# Sheet3.net
KiCad netlist of a schematic drawn in Altium Designer
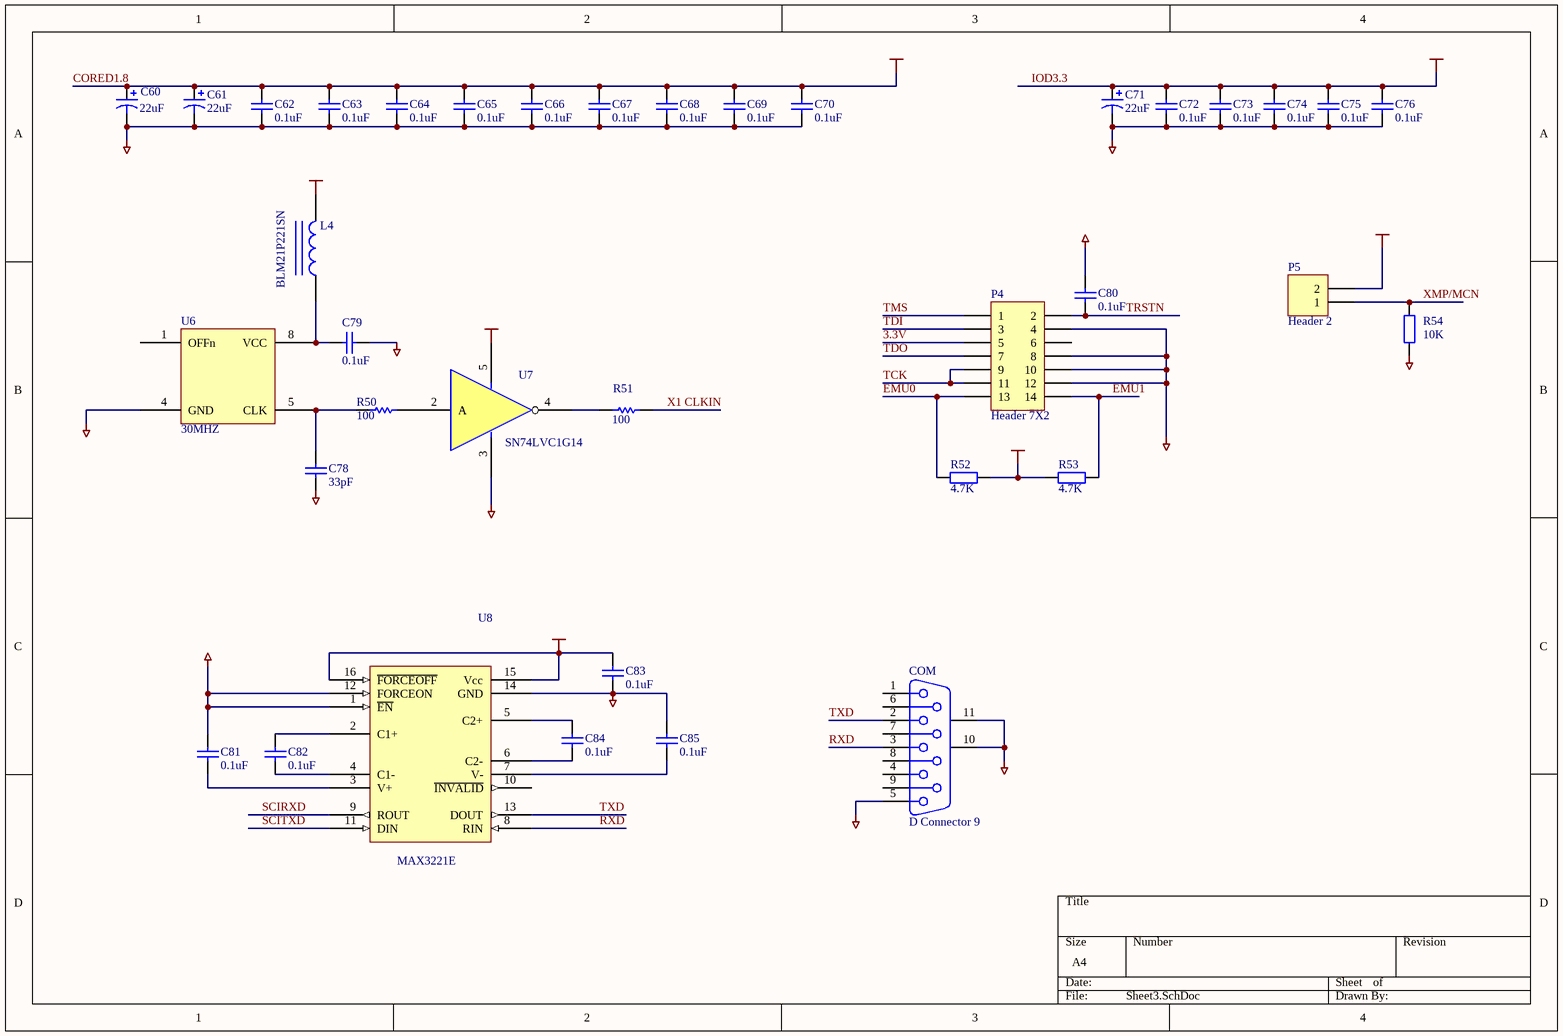
[diagram p0: Sheet3.SchDoc]

(export (version "E")
  (design (tool "Eeschema 10.0.6"))
  (components
    (comp (ref "C60")
      (value "22uF")
      (footprint "CA2222-0350")
      (description "Polarized Capacitor (Surface Mount)")
      (fields (field (name "PUBLISHER") "Altium Limited"))
      (libsource (lib "Miscellaneous Devices") (part "Cap Pol3"))
    )
    (comp (ref "C61")
      (value "22uF")
      (footprint "CA2222-0350")
      (description "Polarized Capacitor (Surface Mount)")
      (fields (field (name "PUBLISHER") "Altium Limited"))
      (libsource (lib "Miscellaneous Devices") (part "Cap Pol3"))
    )
    (comp (ref "C62")
      (value "0.1uF")
      (footprint "CC2012-0805")
      (description "Capacitor (Semiconductor SIM Model)")
      (fields (field (name "PUBLISHER") "Altium Limited"))
      (libsource (lib "Miscellaneous Devices") (part "Cap Semi"))
    )
    (comp (ref "C63")
      (value "0.1uF")
      (footprint "CC2012-0805")
      (description "Capacitor (Semiconductor SIM Model)")
      (fields (field (name "PUBLISHER") "Altium Limited"))
      (libsource (lib "Miscellaneous Devices") (part "Cap Semi"))
    )
    (comp (ref "C64")
      (value "0.1uF")
      (footprint "CC2012-0805")
      (description "Capacitor (Semiconductor SIM Model)")
      (fields (field (name "PUBLISHER") "Altium Limited"))
      (libsource (lib "Miscellaneous Devices") (part "Cap Semi"))
    )
    (comp (ref "C65")
      (value "0.1uF")
      (footprint "CC2012-0805")
      (description "Capacitor (Semiconductor SIM Model)")
      (fields (field (name "PUBLISHER") "Altium Limited"))
      (libsource (lib "Miscellaneous Devices") (part "Cap Semi"))
    )
    (comp (ref "C66")
      (value "0.1uF")
      (footprint "CC2012-0805")
      (description "Capacitor (Semiconductor SIM Model)")
      (fields (field (name "PUBLISHER") "Altium Limited"))
      (libsource (lib "Miscellaneous Devices") (part "Cap Semi"))
    )
    (comp (ref "C67")
      (value "0.1uF")
      (footprint "CC2012-0805")
      (description "Capacitor (Semiconductor SIM Model)")
      (fields (field (name "PUBLISHER") "Altium Limited"))
      (libsource (lib "Miscellaneous Devices") (part "Cap Semi"))
    )
    (comp (ref "C68")
      (value "0.1uF")
      (footprint "CC2012-0805")
      (description "Capacitor (Semiconductor SIM Model)")
      (fields (field (name "PUBLISHER") "Altium Limited"))
      (libsource (lib "Miscellaneous Devices") (part "Cap Semi"))
    )
    (comp (ref "C69")
      (value "0.1uF")
      (footprint "CC2012-0805")
      (description "Capacitor (Semiconductor SIM Model)")
      (fields (field (name "PUBLISHER") "Altium Limited"))
      (libsource (lib "Miscellaneous Devices") (part "Cap Semi"))
    )
    (comp (ref "C70")
      (value "0.1uF")
      (footprint "CC2012-0805")
      (description "Capacitor (Semiconductor SIM Model)")
      (fields (field (name "PUBLISHER") "Altium Limited"))
      (libsource (lib "Miscellaneous Devices") (part "Cap Semi"))
    )
    (comp (ref "C71")
      (value "22uF")
      (footprint "CA2222-0350")
      (description "Polarized Capacitor (Surface Mount)")
      (fields (field (name "PUBLISHER") "Altium Limited"))
      (libsource (lib "Miscellaneous Devices") (part "Cap Pol3"))
    )
    (comp (ref "C72")
      (value "0.1uF")
      (footprint "CC2012-0805")
      (description "Capacitor (Semiconductor SIM Model)")
      (fields (field (name "PUBLISHER") "Altium Limited"))
      (libsource (lib "Miscellaneous Devices") (part "Cap Semi"))
    )
    (comp (ref "C73")
      (value "0.1uF")
      (footprint "CC2012-0805")
      (description "Capacitor (Semiconductor SIM Model)")
      (fields (field (name "PUBLISHER") "Altium Limited"))
      (libsource (lib "Miscellaneous Devices") (part "Cap Semi"))
    )
    (comp (ref "C74")
      (value "0.1uF")
      (footprint "CC2012-0805")
      (description "Capacitor (Semiconductor SIM Model)")
      (fields (field (name "PUBLISHER") "Altium Limited"))
      (libsource (lib "Miscellaneous Devices") (part "Cap Semi"))
    )
    (comp (ref "C75")
      (value "0.1uF")
      (footprint "CC2012-0805")
      (description "Capacitor (Semiconductor SIM Model)")
      (fields (field (name "PUBLISHER") "Altium Limited"))
      (libsource (lib "Miscellaneous Devices") (part "Cap Semi"))
    )
    (comp (ref "C76")
      (value "0.1uF")
      (footprint "CC2012-0805")
      (description "Capacitor")
      (fields (field (name "PUBLISHER") "Altium Limited"))
      (libsource (lib "Miscellaneous Devices") (part "Cap"))
    )
    (comp (ref "C78")
      (value "33pF")
      (footprint "CC2012-0805")
      (description "Capacitor")
      (fields (field (name "PUBLISHER") "Altium Limited"))
      (libsource (lib "Miscellaneous Devices") (part "Cap"))
    )
    (comp (ref "C79")
      (value "0.1uF")
      (footprint "CC2012-0805")
      (description "Capacitor (Semiconductor SIM Model)")
      (fields (field (name "PUBLISHER") "Altium Limited"))
      (libsource (lib "Miscellaneous Devices") (part "Cap Semi"))
    )
    (comp (ref "C80")
      (value "0.1uF")
      (footprint "CC2012-0805")
      (description "Capacitor")
      (fields (field (name "PUBLISHER") "Altium Limited"))
      (libsource (lib "Miscellaneous Devices") (part "Cap"))
    )
    (comp (ref "C81")
      (value "0.1uF")
      (footprint "CC2012-0805")
      (description "Capacitor (Semiconductor SIM Model)")
      (fields (field (name "PUBLISHER") "Altium Limited"))
      (libsource (lib "Miscellaneous Devices") (part "Cap Semi"))
    )
    (comp (ref "C82")
      (value "0.1uF")
      (footprint "CC2012-0805")
      (description "Capacitor (Semiconductor SIM Model)")
      (fields (field (name "PUBLISHER") "Altium Limited"))
      (libsource (lib "Miscellaneous Devices") (part "Cap Semi"))
    )
    (comp (ref "C83")
      (value "0.1uF")
      (footprint "CC2012-0805")
      (description "Capacitor (Semiconductor SIM Model)")
      (fields (field (name "PUBLISHER") "Altium Limited"))
      (libsource (lib "Miscellaneous Devices") (part "Cap Semi"))
    )
    (comp (ref "C84")
      (value "0.1uF")
      (footprint "CC2012-0805")
      (description "Capacitor (Semiconductor SIM Model)")
      (fields (field (name "PUBLISHER") "Altium Limited"))
      (libsource (lib "Miscellaneous Devices") (part "Cap Semi"))
    )
    (comp (ref "C85")
      (value "0.1uF")
      (footprint "CC2012-0805")
      (description "Capacitor (Semiconductor SIM Model)")
      (fields (field (name "PUBLISHER") "Altium Limited"))
      (libsource (lib "Miscellaneous Devices") (part "Cap Semi"))
    )
    (comp (ref "COM")
      (value "D Connector 9")
      (footprint "DSUB1.385-2H9")
      (description "Receptacle Assembly, 9 Position, Right Angle")
      (fields (field (name "PUBLISHER") "Altium Limited"))
      (libsource (lib "Miscellaneous Connectors") (part "D Connector 9"))
    )
    (comp (ref "L4")
      (value "BLM21P221SN")
      (footprint "CR2012-0805")
      (description "Magnetic-Core Inductor")
      (fields (field (name "PUBLISHER") "Altium Limited"))
      (libsource (lib "Miscellaneous Devices") (part "Inductor Iron"))
    )
    (comp (ref "P4")
      (value "Header 7X2")
      (footprint "HDR2X7")
      (description "Header, 7-Pin, Dual row")
      (fields (field (name "PUBLISHER") "Altium Limited"))
      (libsource (lib "Miscellaneous Connectors") (part "Header 7X2"))
    )
    (comp (ref "P5")
      (value "Header 2")
      (footprint "HDR1X2")
      (description "Header, 2-Pin")
      (fields (field (name "PUBLISHER") "Altium Limited"))
      (libsource (lib "Miscellaneous Connectors") (part "Header 2"))
    )
    (comp (ref "R50")
      (value "100")
      (footprint "CR2012-0805")
      (description "Resistor")
      (fields (field (name "PUBLISHER") "Altium Limited"))
      (libsource (lib "Miscellaneous Devices") (part "Res1"))
    )
    (comp (ref "R51")
      (value "100")
      (footprint "CR2012-0805")
      (description "Resistor")
      (fields (field (name "PUBLISHER") "Altium Limited"))
      (libsource (lib "Miscellaneous Devices") (part "Res1"))
    )
    (comp (ref "R52")
      (value "4.7K")
      (footprint "CR2012-0805")
      (description "Resistor")
      (fields (field (name "PUBLISHER") "Altium Limited"))
      (libsource (lib "") (part "Res2_1"))
    )
    (comp (ref "R53")
      (value "4.7K")
      (footprint "CR2012-0805")
      (description "Resistor")
      (fields (field (name "PUBLISHER") "Altium Limited"))
      (libsource (lib "") (part "Res2_1"))
    )
    (comp (ref "R54")
      (value "10K")
      (footprint "CR2012-0805")
      (description "Resistor")
      (fields (field (name "PUBLISHER") "Altium Limited"))
      (libsource (lib "Miscellaneous Devices") (part "Res2"))
    )
    (comp (ref "U6")
      (value "30MHZ")
      (footprint "CR1525-4850")
      (description "有源晶振")
      (libsource (lib "MyIntLib") (part "Crystal"))
    )
    (comp (ref "U7")
      (value "SN74LVC1G14")
      (footprint "SC-70")
      (libsource (lib "MyIntLib") (part "SN74LVC1G14"))
    )
    (comp (ref "U8") (value "MAX3221E") (footprint "PW16") (libsource (lib "Schlib1") (part "MAX3221E")))
  )
  (nets
    (net (code "1") (name "/EMU0") (class "Default")
      (node (ref "P4") (pin "13") (pinfunction "13_13") (pintype "passive"))
      (node (ref "R52") (pin "1") (pinfunction "1_1") (pintype "passive"))
    )
    (net (code "2") (name "/EMU1") (class "Default")
      (node (ref "P4") (pin "14") (pinfunction "14_14") (pintype "passive"))
      (node (ref "R53") (pin "2") (pinfunction "2_2") (pintype "passive"))
    )
    (net (code "3") (name "/RXD") (class "Default")
      (node (ref "COM") (pin "3") (pinfunction "3_3") (pintype "passive"))
      (node (ref "U8") (pin "8") (pinfunction "RIN_8") (pintype "input"))
    )
    (net (code "4") (name "/SCIRXD") (class "Default")
      (node (ref "U8") (pin "9") (pinfunction "ROUT_9") (pintype "output"))
    )
    (net (code "5") (name "/SCITXD") (class "Default")
      (node (ref "U8") (pin "11") (pinfunction "DIN_11") (pintype "input"))
    )
    (net (code "6") (name "/TCK") (class "Default")
      (node (ref "P4") (pin "11") (pinfunction "11_11") (pintype "passive"))
      (node (ref "P4") (pin "9") (pinfunction "9_9") (pintype "passive"))
    )
    (net (code "7") (name "/TDI") (class "Default")
      (node (ref "P4") (pin "3") (pinfunction "3_3") (pintype "passive"))
    )
    (net (code "8") (name "/TDO") (class "Default")
      (node (ref "P4") (pin "7") (pinfunction "7_7") (pintype "passive"))
    )
    (net (code "9") (name "/TMS") (class "Default")
      (node (ref "P4") (pin "1") (pinfunction "1_1") (pintype "passive"))
    )
    (net (code "10") (name "/TRSTN") (class "Default")
      (node (ref "C80") (pin "1") (pinfunction "1_1") (pintype "passive"))
      (node (ref "P4") (pin "2") (pinfunction "2_2") (pintype "passive"))
    )
    (net (code "11") (name "/TXD") (class "Default")
      (node (ref "COM") (pin "2") (pinfunction "2_2") (pintype "passive"))
      (node (ref "U8") (pin "13") (pinfunction "DOUT_13") (pintype "output"))
    )
    (net (code "12") (name "/X1 CLKIN") (class "Default")
      (node (ref "R51") (pin "2") (pinfunction "2_2") (pintype "passive"))
    )
    (net (code "13") (name "/XMP{slash}MCN") (class "Default")
      (node (ref "P5") (pin "1") (pinfunction "1_1") (pintype "passive"))
      (node (ref "R54") (pin "2") (pinfunction "2_2") (pintype "passive"))
    )
    (net (code "14") (name "1.8V") (class "Default")
      (node (ref "C60") (pin "1") (pinfunction "1_1") (pintype "passive"))
      (node (ref "C61") (pin "1") (pinfunction "1_1") (pintype "passive"))
      (node (ref "C62") (pin "2") (pinfunction "2_2") (pintype "passive"))
      (node (ref "C63") (pin "2") (pinfunction "2_2") (pintype "passive"))
      (node (ref "C64") (pin "2") (pinfunction "2_2") (pintype "passive"))
      (node (ref "C65") (pin "2") (pinfunction "2_2") (pintype "passive"))
      (node (ref "C66") (pin "2") (pinfunction "2_2") (pintype "passive"))
      (node (ref "C67") (pin "2") (pinfunction "2_2") (pintype "passive"))
      (node (ref "C68") (pin "2") (pinfunction "2_2") (pintype "passive"))
      (node (ref "C69") (pin "2") (pinfunction "2_2") (pintype "passive"))
      (node (ref "C70") (pin "2") (pinfunction "2_2") (pintype "passive"))
      (node (ref "U7") (pin "5") (pinfunction "VCC_5") (pintype "power_in"))
    )
    (net (code "15") (name "3.3V") (class "Default")
      (node (ref "C71") (pin "1") (pinfunction "1_1") (pintype "passive"))
      (node (ref "C72") (pin "2") (pinfunction "2_2") (pintype "passive"))
      (node (ref "C73") (pin "2") (pinfunction "2_2") (pintype "passive"))
      (node (ref "C74") (pin "2") (pinfunction "2_2") (pintype "passive"))
      (node (ref "C75") (pin "2") (pinfunction "2_2") (pintype "passive"))
      (node (ref "C76") (pin "2") (pinfunction "2_2") (pintype "passive"))
      (node (ref "C83") (pin "2") (pinfunction "2_2") (pintype "passive"))
      (node (ref "L4") (pin "2") (pinfunction "2_2") (pintype "passive"))
      (node (ref "P4") (pin "5") (pinfunction "5_5") (pintype "passive"))
      (node (ref "P5") (pin "2") (pinfunction "2_2") (pintype "passive"))
      (node (ref "R52") (pin "2") (pinfunction "2_2") (pintype "passive"))
      (node (ref "R53") (pin "1") (pinfunction "1_1") (pintype "passive"))
      (node (ref "U8") (pin "15") (pinfunction "Vcc_15") (pintype "power_in"))
      (node (ref "U8") (pin "16") (pinfunction "~{FORCEOFF}_16") (pintype "input"))
    )
    (net (code "16") (name "DGND") (class "Default")
      (node (ref "C60") (pin "2") (pinfunction "2_2") (pintype "passive"))
      (node (ref "C61") (pin "2") (pinfunction "2_2") (pintype "passive"))
      (node (ref "C62") (pin "1") (pinfunction "1_1") (pintype "passive"))
      (node (ref "C63") (pin "1") (pinfunction "1_1") (pintype "passive"))
      (node (ref "C64") (pin "1") (pinfunction "1_1") (pintype "passive"))
      (node (ref "C65") (pin "1") (pinfunction "1_1") (pintype "passive"))
      (node (ref "C66") (pin "1") (pinfunction "1_1") (pintype "passive"))
      (node (ref "C67") (pin "1") (pinfunction "1_1") (pintype "passive"))
      (node (ref "C68") (pin "1") (pinfunction "1_1") (pintype "passive"))
      (node (ref "C69") (pin "1") (pinfunction "1_1") (pintype "passive"))
      (node (ref "C70") (pin "1") (pinfunction "1_1") (pintype "passive"))
      (node (ref "C71") (pin "2") (pinfunction "2_2") (pintype "passive"))
      (node (ref "C72") (pin "1") (pinfunction "1_1") (pintype "passive"))
      (node (ref "C73") (pin "1") (pinfunction "1_1") (pintype "passive"))
      (node (ref "C74") (pin "1") (pinfunction "1_1") (pintype "passive"))
      (node (ref "C75") (pin "1") (pinfunction "1_1") (pintype "passive"))
      (node (ref "C76") (pin "1") (pinfunction "1_1") (pintype "passive"))
      (node (ref "C78") (pin "1") (pinfunction "1_1") (pintype "passive"))
      (node (ref "C79") (pin "2") (pinfunction "2_2") (pintype "passive"))
      (node (ref "C80") (pin "2") (pinfunction "2_2") (pintype "passive"))
      (node (ref "C81") (pin "2") (pinfunction "2_2") (pintype "passive"))
      (node (ref "C83") (pin "1") (pinfunction "1_1") (pintype "passive"))
      (node (ref "C85") (pin "2") (pinfunction "2_2") (pintype "passive"))
      (node (ref "COM") (pin "10") (pinfunction "MH1_10") (pintype "passive"))
      (node (ref "COM") (pin "11") (pinfunction "MH2_11") (pintype "passive"))
      (node (ref "COM") (pin "5") (pinfunction "5_5") (pintype "passive"))
      (node (ref "P4") (pin "10") (pinfunction "10_10") (pintype "passive"))
      (node (ref "P4") (pin "12") (pinfunction "12_12") (pintype "passive"))
      (node (ref "P4") (pin "4") (pinfunction "4_4") (pintype "passive"))
      (node (ref "P4") (pin "8") (pinfunction "8_8") (pintype "passive"))
      (node (ref "R54") (pin "1") (pinfunction "1_1") (pintype "passive"))
      (node (ref "U6") (pin "4") (pinfunction "GND_4") (pintype "power_in"))
      (node (ref "U7") (pin "3") (pinfunction "GND_3") (pintype "power_in"))
      (node (ref "U8") (pin "1") (pinfunction "~{EN}_1") (pintype "input"))
      (node (ref "U8") (pin "12") (pinfunction "FORCEON_12") (pintype "input"))
      (node (ref "U8") (pin "14") (pinfunction "GND_14") (pintype "power_in"))
    )
    (net (code "17") (name "Net-(U6-CLK)") (class "Default")
      (node (ref "C78") (pin "2") (pinfunction "2_2") (pintype "passive"))
      (node (ref "R50") (pin "1") (pinfunction "1_1") (pintype "passive"))
      (node (ref "U6") (pin "5") (pinfunction "CLK_5") (pintype "passive"))
    )
    (net (code "18") (name "Net-(U6-VCC)") (class "Default")
      (node (ref "C79") (pin "1") (pinfunction "1_1") (pintype "passive"))
      (node (ref "L4") (pin "1") (pinfunction "1_1") (pintype "passive"))
      (node (ref "U6") (pin "8") (pinfunction "VCC_8") (pintype "power_in"))
    )
    (net (code "19") (name "Net-(U7-A)") (class "Default")
      (node (ref "R50") (pin "2") (pinfunction "2_2") (pintype "passive"))
      (node (ref "U7") (pin "2") (pinfunction "A_2") (pintype "passive"))
    )
    (net (code "20") (name "Net-(U7-Y)") (class "Default")
      (node (ref "R51") (pin "1") (pinfunction "1_1") (pintype "passive"))
      (node (ref "U7") (pin "4") (pinfunction "Y_4") (pintype "passive"))
    )
    (net (code "21") (name "Net-(U8-C1+)") (class "Default")
      (node (ref "C82") (pin "2") (pinfunction "2_2") (pintype "passive"))
      (node (ref "U8") (pin "2") (pinfunction "C1+_2") (pintype "passive"))
    )
    (net (code "22") (name "Net-(U8-C1-)") (class "Default")
      (node (ref "C82") (pin "1") (pinfunction "1_1") (pintype "passive"))
      (node (ref "U8") (pin "4") (pinfunction "C1-_4") (pintype "passive"))
    )
    (net (code "23") (name "Net-(U8-C2+)") (class "Default")
      (node (ref "C84") (pin "2") (pinfunction "2_2") (pintype "passive"))
      (node (ref "U8") (pin "5") (pinfunction "C2+_5") (pintype "passive"))
    )
    (net (code "24") (name "Net-(U8-C2-)") (class "Default")
      (node (ref "C84") (pin "1") (pinfunction "1_1") (pintype "passive"))
      (node (ref "U8") (pin "6") (pinfunction "C2-_6") (pintype "passive"))
    )
    (net (code "25") (name "Net-(U8-V+)") (class "Default")
      (node (ref "C81") (pin "1") (pinfunction "1_1") (pintype "passive"))
      (node (ref "U8") (pin "3") (pinfunction "V+_3") (pintype "passive"))
    )
    (net (code "26") (name "Net-(U8-V-)") (class "Default")
      (node (ref "C85") (pin "1") (pinfunction "1_1") (pintype "passive"))
      (node (ref "U8") (pin "7") (pinfunction "V-_7") (pintype "passive"))
    )
    (net (code "27") (name "unconnected-(COM-Pad1)") (class "Default")
      (node (ref "COM") (pin "1") (pinfunction "1_1") (pintype "passive"))
    )
    (net (code "28") (name "unconnected-(COM-Pad4)") (class "Default")
      (node (ref "COM") (pin "4") (pinfunction "4_4") (pintype "passive"))
    )
    (net (code "29") (name "unconnected-(COM-Pad6)") (class "Default")
      (node (ref "COM") (pin "6") (pinfunction "6_6") (pintype "passive"))
    )
    (net (code "30") (name "unconnected-(COM-Pad7)") (class "Default")
      (node (ref "COM") (pin "7") (pinfunction "7_7") (pintype "passive"))
    )
    (net (code "31") (name "unconnected-(COM-Pad8)") (class "Default")
      (node (ref "COM") (pin "8") (pinfunction "8_8") (pintype "passive"))
    )
    (net (code "32") (name "unconnected-(COM-Pad9)") (class "Default")
      (node (ref "COM") (pin "9") (pinfunction "9_9") (pintype "passive"))
    )
    (net (code "33") (name "unconnected-(P4-Pad6)") (class "Default")
      (node (ref "P4") (pin "6") (pinfunction "6_6") (pintype "passive"))
    )
    (net (code "34") (name "unconnected-(U6-OFFn-Pad1)") (class "Default")
      (node (ref "U6") (pin "1") (pinfunction "OFFn_1") (pintype "passive"))
    )
    (net (code "35") (name "unconnected-(U7-NC-Pad1)") (class "Default")
      (node (ref "U7") (pin "1") (pinfunction "NC_1") (pintype "passive"))
    )
    (net (code "36") (name "unconnected-(U8-~{INVALID}-Pad10)") (class "Default")
      (node (ref "U8") (pin "10") (pinfunction "~{INVALID}_10") (pintype "output"))
    )
  )
)
